# 3_6_1--esp32_-_1031_I2S.net
KiCad netlist of a schematic drawn in EasyEDA Pro
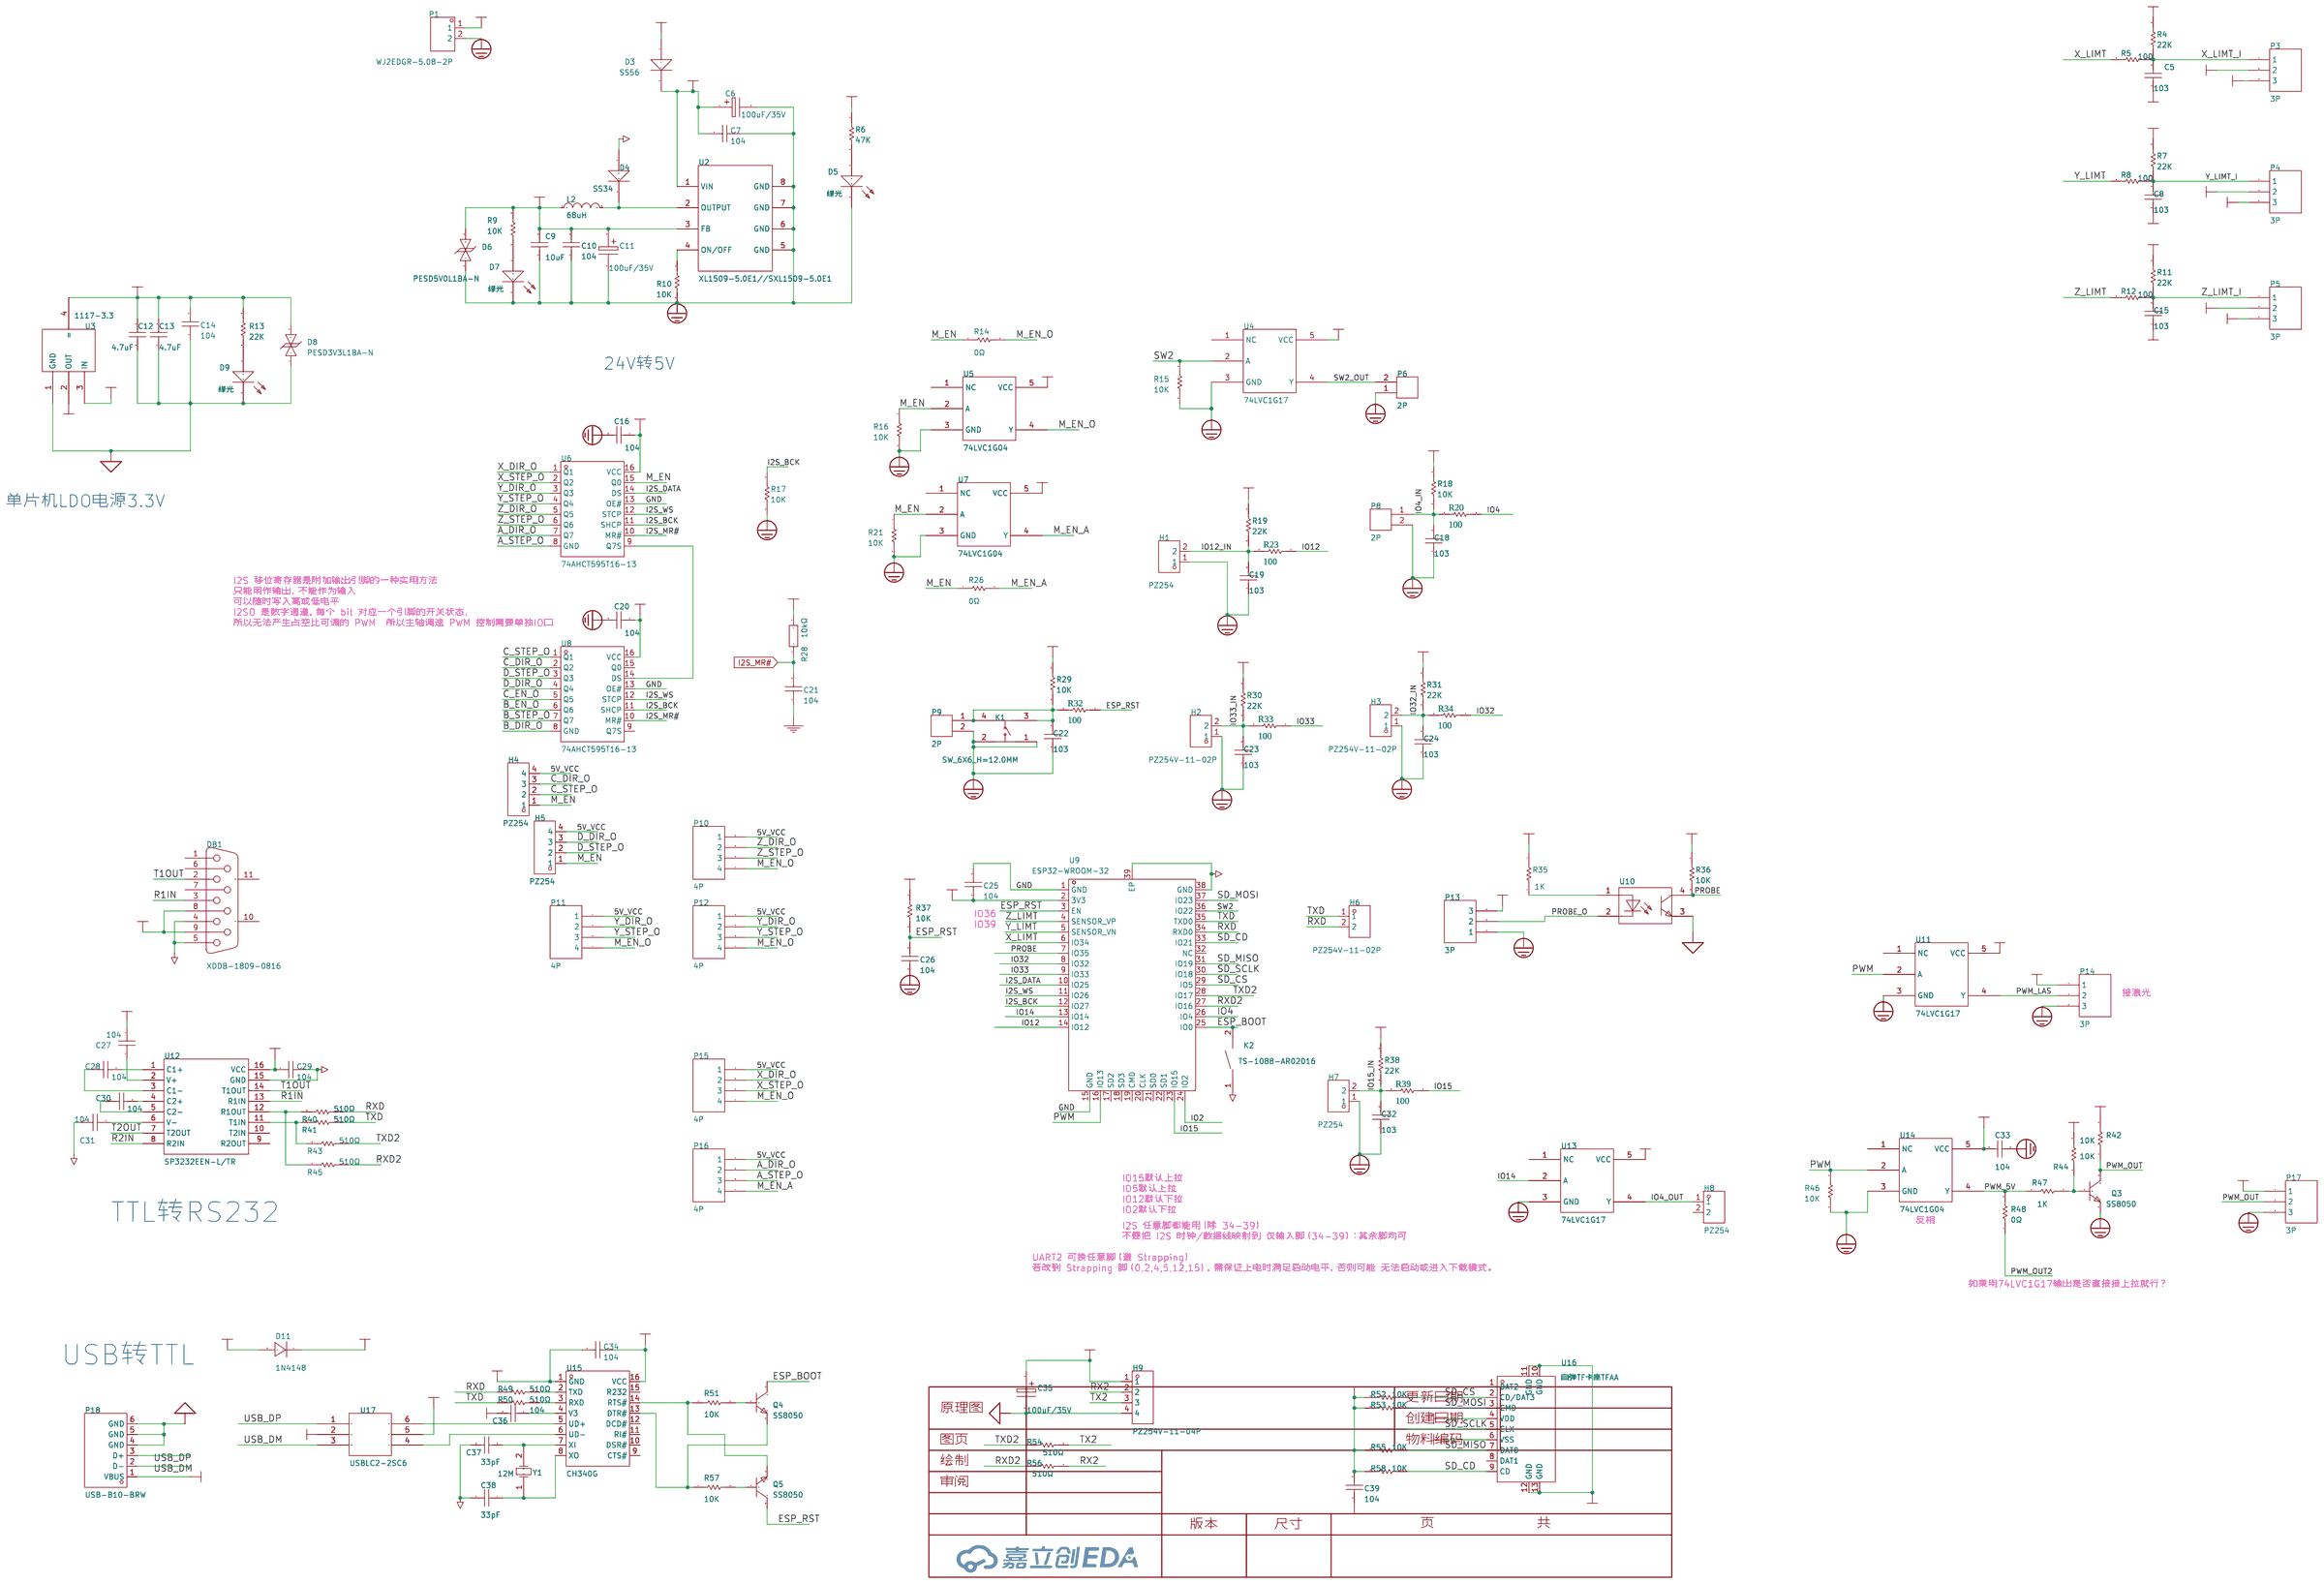
[diagram p0: schematic sheet]

(export (version "E")
  (design (tool "Eeschema 10.0.6"))
  (components
    (comp (ref "C5") (value "103") (footprint "easyedapro:11") (libsource (lib "easyedapro") (part "CAP")))
    (comp (ref "C6")
      (value "100uF/35V")
      (footprint "easyedapro:电解电容贴片10x10")
      (libsource (lib "easyedapro") (part "ELECTRO1"))
    )
    (comp (ref "C7")
      (value "104")
      (footprint "easyedapro:0603C")
      (description "Capacitor (Semiconductor SIM Model)")
      (libsource (lib "easyedapro") (part "Cap Semi"))
    )
    (comp (ref "C8") (value "103") (footprint "easyedapro:11") (libsource (lib "easyedapro") (part "CAP")))
    (comp (ref "C9") (value "10uF") (libsource (lib "") (part "CAP_1")))
    (comp (ref "C10")
      (value "104")
      (footprint "easyedapro:0603C")
      (description "Capacitor (Semiconductor SIM Model)")
      (libsource (lib "easyedapro") (part "Cap Semi"))
    )
    (comp (ref "C11")
      (value "100uF/35V")
      (footprint "easyedapro:0603C")
      (libsource (lib "easyedapro") (part "ELECTRO1"))
    )
    (comp (ref "C12") (value "4.7uF") (libsource (lib "") (part "CAP_1")))
    (comp (ref "C13") (value "4.7uF") (libsource (lib "") (part "CAP_1")))
    (comp (ref "C14")
      (value "104")
      (footprint "easyedapro:0603C")
      (description "Capacitor (Semiconductor SIM Model)")
      (libsource (lib "easyedapro") (part "Cap Semi"))
    )
    (comp (ref "C15") (value "103") (footprint "easyedapro:11") (libsource (lib "easyedapro") (part "CAP")))
    (comp (ref "C16")
      (value "104")
      (footprint "easyedapro:0603C")
      (description "Capacitor (Semiconductor SIM Model)")
      (libsource (lib "easyedapro") (part "Cap Semi"))
    )
    (comp (ref "C18") (value "103") (footprint "easyedapro:11") (libsource (lib "easyedapro") (part "CAP")))
    (comp (ref "C19") (value "103") (footprint "easyedapro:11") (libsource (lib "easyedapro") (part "CAP")))
    (comp (ref "C20")
      (value "104")
      (footprint "easyedapro:0603C")
      (description "Capacitor (Semiconductor SIM Model)")
      (libsource (lib "easyedapro") (part "Cap Semi"))
    )
    (comp (ref "C21")
      (value "104")
      (footprint "easyedapro:0603C")
      (description "Capacitor (Semiconductor SIM Model)")
      (libsource (lib "easyedapro") (part "Cap Semi"))
    )
    (comp (ref "C22") (value "103") (footprint "easyedapro:11") (libsource (lib "easyedapro") (part "CAP")))
    (comp (ref "C23") (value "103") (footprint "easyedapro:11") (libsource (lib "easyedapro") (part "CAP")))
    (comp (ref "C24") (value "103") (footprint "easyedapro:11") (libsource (lib "easyedapro") (part "CAP")))
    (comp (ref "C25")
      (value "104")
      (footprint "easyedapro:0603C")
      (description "Capacitor (Semiconductor SIM Model)")
      (libsource (lib "easyedapro") (part "Cap Semi"))
    )
    (comp (ref "C26")
      (value "104")
      (footprint "easyedapro:0603C")
      (description "Capacitor (Semiconductor SIM Model)")
      (libsource (lib "easyedapro") (part "Cap Semi"))
    )
    (comp (ref "C27")
      (value "104")
      (footprint "easyedapro:0603C")
      (description "Capacitor (Semiconductor SIM Model)")
      (libsource (lib "easyedapro") (part "Cap Semi"))
    )
    (comp (ref "C28")
      (value "104")
      (footprint "easyedapro:0603C")
      (description "Capacitor (Semiconductor SIM Model)")
      (libsource (lib "easyedapro") (part "Cap Semi"))
    )
    (comp (ref "C29")
      (value "104")
      (footprint "easyedapro:0603C")
      (description "Capacitor (Semiconductor SIM Model)")
      (libsource (lib "easyedapro") (part "Cap Semi"))
    )
    (comp (ref "C30")
      (value "104")
      (footprint "easyedapro:0603C")
      (description "Capacitor (Semiconductor SIM Model)")
      (libsource (lib "easyedapro") (part "Cap Semi"))
    )
    (comp (ref "C31")
      (value "104")
      (footprint "easyedapro:0603C")
      (description "Capacitor (Semiconductor SIM Model)")
      (libsource (lib "easyedapro") (part "Cap Semi"))
    )
    (comp (ref "C32") (value "103") (footprint "easyedapro:11") (libsource (lib "easyedapro") (part "CAP")))
    (comp (ref "C33")
      (value "104")
      (footprint "easyedapro:0603C")
      (description "Capacitor (Semiconductor SIM Model)")
      (libsource (lib "easyedapro") (part "Cap Semi"))
    )
    (comp (ref "C34")
      (value "104")
      (footprint "easyedapro:0603C")
      (description "Capacitor (Semiconductor SIM Model)")
      (libsource (lib "easyedapro") (part "Cap Semi"))
    )
    (comp (ref "C35")
      (value "100uF/35V")
      (footprint "easyedapro:电解电容贴片10x10")
      (libsource (lib "easyedapro") (part "ELECTRO1"))
    )
    (comp (ref "C36")
      (value "104")
      (footprint "easyedapro:0603C")
      (description "Capacitor (Semiconductor SIM Model)")
      (libsource (lib "easyedapro") (part "Cap Semi"))
    )
    (comp (ref "C37")
      (value "18pF")
      (footprint "easyedapro:0603C")
      (description "Capacitor (Semiconductor SIM Model)")
      (libsource (lib "easyedapro") (part "Cap Semi"))
    )
    (comp (ref "C38")
      (value "18pF")
      (footprint "easyedapro:0603C")
      (description "Capacitor (Semiconductor SIM Model)")
      (libsource (lib "easyedapro") (part "Cap Semi"))
    )
    (comp (ref "C39")
      (value "104")
      (footprint "easyedapro:11")
      (description "Capacitor (Semiconductor SIM Model)")
      (libsource (lib "easyedapro") (part "Cap Semi"))
    )
    (comp (ref "D3") (value "SS56") (footprint "easyedapro:SMA") (libsource (lib "") (part "1N4148_1")))
    (comp (ref "D4") (value "SS34") (libsource (lib "easyedapro") (part "1N4148")))
    (comp (ref "D5")
      (value "绿光")
      (footprint "easyedapro:0603LED")
      (libsource (lib "easyedapro") (part "LED"))
    )
    (comp (ref "D6")
      (value "PESD5V0L1BA-N")
      (footprint "easyedapro:SOD-523_L1.2-W0.8-LS1.6-BI")
      (description "极性:Bidirectional;反向关断电压（典型值）:5V (Max);击穿电压（最小值）:6V;箝位电压:15V;峰值脉冲电流（10/1000us）:5A (8/20us);")
      (fields (field (name "Manufacturer") "BORN伯恩半导体"))
      (libsource (lib "easyedapro") (part "PESD5V0S1BBN"))
    )
    (comp (ref "D7")
      (value "绿光")
      (footprint "easyedapro:0603LED")
      (libsource (lib "easyedapro") (part "LED"))
    )
    (comp (ref "D8")
      (value "PESD3V3L1BA-N")
      (footprint "easyedapro:SOD-523_L1.2-W0.8-LS1.6-BI")
      (description "极性:Bidirectional;反向关断电压（典型值）:5V (Max);击穿电压（最小值）:6V;箝位电压:15V;峰值脉冲电流（10/1000us）:5A (8/20us);")
      (fields (field (name "Manufacturer") "BORN伯恩半导体"))
      (libsource (lib "easyedapro") (part "PESD5V0S1BBN"))
    )
    (comp (ref "D9")
      (value "绿光")
      (footprint "easyedapro:0603LED")
      (libsource (lib "easyedapro") (part "LED"))
    )
    (comp (ref "D11")
      (value "1N4148")
      (footprint "easyedapro:SOD-123_L2.8-W1.8-LS3.7-RD")
      (fields (field (name "Manufacturer") "VISHAY(威世)"))
      (libsource (lib "easyedapro") (part "1N4148W-E3-08"))
    )
    (comp (ref "DB1")
      (value "XDDB-1809-0816")
      (footprint "easyedapro:DB9-TH_LD09P33E4GV00LF")
      (description "连接器类型:常规D-Sub;公母:公;总PIN位数:9P;安装方式:弯插;排数:2;额定电流-信号脚:3A;工作温度范围:-40°C~+85°C;")
      (fields (field (name "Manufacturer") "LX(连欣科技)"))
      (libsource (lib "easyedapro") (part "XDDB-1809-0816"))
    )
    (comp (ref "H1")
      (value "PZ254")
      (footprint "easyedapro:HDR-TH_2P-P2.54-V-M")
      (fields (field (name "Manufacturer") "XFCN(兴飞)"))
      (libsource (lib "easyedapro") (part "PZ254V-11-02P"))
    )
    (comp (ref "H2")
      (value "PZ254V-11-02P")
      (footprint "easyedapro:HDR-TH_2P-P2.54-V-M")
      (fields (field (name "Manufacturer") "XFCN(兴飞)"))
      (libsource (lib "easyedapro") (part "PZ254V-11-02P"))
    )
    (comp (ref "H3")
      (value "PZ254V-11-02P")
      (footprint "easyedapro:HDR-TH_2P-P2.54-V-M")
      (fields (field (name "Manufacturer") "XFCN(兴飞)"))
      (libsource (lib "easyedapro") (part "PZ254V-11-02P"))
    )
    (comp (ref "H4")
      (value "PZ254")
      (footprint "easyedapro:HDR-TH_4P-P2.54-V-M")
      (fields (field (name "Manufacturer") "XFCN(兴飞)"))
      (libsource (lib "easyedapro") (part "PZ254V-11-04P_C2691448"))
    )
    (comp (ref "H5")
      (value "PZ254")
      (footprint "easyedapro:HDR-TH_4P-P2.54-V-M")
      (fields (field (name "Manufacturer") "XFCN(兴飞)"))
      (libsource (lib "easyedapro") (part "PZ254V-11-04P_C2691448"))
    )
    (comp (ref "H6")
      (value "PZ254V-11-02P")
      (footprint "easyedapro:HDR-TH_2P-P2.54-V-M")
      (fields (field (name "Manufacturer") "XFCN(兴飞)"))
      (libsource (lib "easyedapro") (part "PZ254V-11-02P"))
    )
    (comp (ref "H7")
      (value "PZ254")
      (footprint "easyedapro:HDR-TH_2P-P2.54-V-M")
      (fields (field (name "Manufacturer") "XFCN(兴飞)"))
      (libsource (lib "easyedapro") (part "PZ254V-11-02P"))
    )
    (comp (ref "H8")
      (value "PZ254")
      (footprint "easyedapro:HDR-TH_2P-P2.54-V-M")
      (fields (field (name "Manufacturer") "XFCN(兴飞)"))
      (libsource (lib "easyedapro") (part "PZ254V-11-02P"))
    )
    (comp (ref "H9")
      (value "PZ254V-11-04P")
      (footprint "easyedapro:HDR-TH_4P-P2.54-V-M")
      (fields (field (name "Manufacturer") "XFCN(兴飞)"))
      (libsource (lib "easyedapro") (part "PZ254V-11-04P_C2691448"))
    )
    (comp (ref "K1")
      (value "SW_6X6_H=12.0MM")
      (footprint "easyedapro:KEY-SMD_4P-L6.0-W6.0-P4.50-LS9.0")
      (libsource (lib "easyedapro") (part "SW_6X6_H=12.0MM"))
    )
    (comp (ref "K2")
      (value "TS-1088-AR02016")
      (footprint "easyedapro:SW-SMD_L3.9-W3.0-P4.45")
      (fields (field (name "Manufacturer") "XUNPU(讯普)"))
      (libsource (lib "easyedapro") (part "TS-1088-AR02016"))
    )
    (comp (ref "L2")
      (value "68uH")
      (footprint "easyedapro:IND-SMD_L7.0-W7.0_SMDRI74-330MT")
      (description "电感值:33uH;精度:±20%;额定电流:960mA;饱和电流(Isat):1.8A;类型:屏蔽电感;")
      (fields (field (name "Manufacturer Part") "SMDRI74-330MT") (field (name "Manufacturer") "SXN(顺翔诺)"))
      (libsource (lib "easyedapro") (part "SMDRI74-330MT"))
    )
    (comp (ref "P1")
      (value "WJ2EDGR-5.08-2P")
      (footprint "easyedapro:CONN-TH_WJ2EDGR-5.08-2P")
      (description "每排PIN数:2;安装方式:弯针;排数:1;间距:5.08mm;连接器类型:板端/插座-开口;")
      (fields (field (name "Manufacturer") "KANGNEX(康奈克斯电气)"))
      (libsource (lib "easyedapro") (part "WJ2EDGR-5.08-2P"))
    )
    (comp (ref "P3")
      (value "3P")
      (footprint "easyedapro:HDR1X3_CON")
      (libsource (lib "easyedapro") (part "3P"))
    )
    (comp (ref "P4")
      (value "3P")
      (footprint "easyedapro:HDR1X3_CON")
      (libsource (lib "easyedapro") (part "3P"))
    )
    (comp (ref "P5")
      (value "3P")
      (footprint "easyedapro:HDR1X3_CON")
      (libsource (lib "easyedapro") (part "3P"))
    )
    (comp (ref "P6") (value "2P") (libsource (lib "easyedapro") (part "2P")))
    (comp (ref "P8") (value "2P") (libsource (lib "easyedapro") (part "2P")))
    (comp (ref "P9") (value "2P") (libsource (lib "easyedapro") (part "2P")))
    (comp (ref "P10")
      (value "4P")
      (footprint "easyedapro:HDR1X4_CON")
      (libsource (lib "easyedapro") (part "4P"))
    )
    (comp (ref "P11")
      (value "4P")
      (footprint "easyedapro:HDR1X4_CON")
      (libsource (lib "easyedapro") (part "4P"))
    )
    (comp (ref "P12")
      (value "4P")
      (footprint "easyedapro:HDR1X4_CON")
      (libsource (lib "easyedapro") (part "4P"))
    )
    (comp (ref "P13")
      (value "3P")
      (footprint "easyedapro:HDR1X3_CON")
      (libsource (lib "easyedapro") (part "3P"))
    )
    (comp (ref "P14")
      (value "3P")
      (footprint "easyedapro:HDR1X3_CON")
      (libsource (lib "easyedapro") (part "3P"))
    )
    (comp (ref "P15")
      (value "4P")
      (footprint "easyedapro:HDR1X4_CON")
      (libsource (lib "easyedapro") (part "4P"))
    )
    (comp (ref "P16")
      (value "4P")
      (footprint "easyedapro:HDR1X4_CON")
      (libsource (lib "easyedapro") (part "4P"))
    )
    (comp (ref "P17")
      (value "3P")
      (footprint "easyedapro:HDR1X3_CON")
      (libsource (lib "easyedapro") (part "3P"))
    )
    (comp (ref "P18")
      (value "USB-B10-BRW")
      (footprint "easyedapro:USB-B-TH_USB-B10-BRW")
      (fields (field (name "Manufacturer") "XUNPU(讯普)"))
      (libsource (lib "easyedapro") (part "USB-B10-BRW"))
    )
    (comp (ref "Q3")
      (value "SS8050")
      (footprint "easyedapro:SOT-23-3_L2.9-W1.3-P1.90-LS2.4-BR")
      (fields (field (name "Manufacturer") "CJ（江苏长电/长晶）"))
      (libsource (lib "easyedapro") (part "SS8050_C2150"))
    )
    (comp (ref "Q4")
      (value "SS8050")
      (footprint "easyedapro:SOT-23-3_L2.9-W1.3-P1.90-LS2.4-BR")
      (fields (field (name "Manufacturer") "Doeshare(德芯)"))
      (libsource (lib "easyedapro") (part "SS8050_C2931717"))
    )
    (comp (ref "Q5")
      (value "SS8050")
      (footprint "easyedapro:SOT-23-3_L2.9-W1.3-P1.90-LS2.4-BR")
      (fields (field (name "Manufacturer") "Doeshare(德芯)"))
      (libsource (lib "easyedapro") (part "SS8050_C2931717"))
    )
    (comp (ref "R4")
      (value "22K")
      (footprint "easyedapro:10")
      (description "Resistor")
      (libsource (lib "easyedapro") (part "RES"))
    )
    (comp (ref "R5")
      (value "100")
      (footprint "easyedapro:10")
      (description "Resistor")
      (libsource (lib "easyedapro") (part "RES"))
    )
    (comp (ref "R6")
      (value "47K")
      (footprint "easyedapro:0603R")
      (description "Resistor")
      (libsource (lib "easyedapro") (part "RES"))
    )
    (comp (ref "R7")
      (value "22K")
      (footprint "easyedapro:10")
      (description "Resistor")
      (libsource (lib "easyedapro") (part "RES"))
    )
    (comp (ref "R8")
      (value "100")
      (footprint "easyedapro:10")
      (description "Resistor")
      (libsource (lib "easyedapro") (part "RES"))
    )
    (comp (ref "R9")
      (value "10K")
      (footprint "easyedapro:0603R")
      (description "Resistor")
      (libsource (lib "easyedapro") (part "RES"))
    )
    (comp (ref "R10")
      (value "10K")
      (footprint "easyedapro:0603R")
      (description "Resistor")
      (libsource (lib "easyedapro") (part "RES"))
    )
    (comp (ref "R11")
      (value "22K")
      (footprint "easyedapro:10")
      (description "Resistor")
      (libsource (lib "easyedapro") (part "RES"))
    )
    (comp (ref "R12")
      (value "100")
      (footprint "easyedapro:10")
      (description "Resistor")
      (libsource (lib "easyedapro") (part "RES"))
    )
    (comp (ref "R13")
      (value "10K")
      (footprint "easyedapro:0603R")
      (description "Resistor")
      (libsource (lib "easyedapro") (part "RES"))
    )
    (comp (ref "R14")
      (value "0Ω")
      (description "Resistor")
      (fields (field (name "Publisher") "Altium Limited"))
      (libsource (lib "") (part "RES_1"))
    )
    (comp (ref "R15")
      (value "10K")
      (description "Resistor")
      (fields (field (name "Publisher") "Altium Limited"))
      (libsource (lib "") (part "RES_1"))
    )
    (comp (ref "R16")
      (value "10K")
      (description "Resistor")
      (fields (field (name "Publisher") "Altium Limited"))
      (libsource (lib "") (part "RES_1"))
    )
    (comp (ref "R17")
      (value "10K")
      (footprint "easyedapro:0603R")
      (description "Resistor")
      (libsource (lib "easyedapro") (part "RES"))
    )
    (comp (ref "R18")
      (value "10K")
      (footprint "easyedapro:0603R")
      (description "Resistor")
      (libsource (lib "easyedapro") (part "RES"))
    )
    (comp (ref "R19")
      (value "10K")
      (footprint "easyedapro:0603R")
      (description "Resistor")
      (libsource (lib "easyedapro") (part "RES"))
    )
    (comp (ref "R20")
      (value "100")
      (description "Resistor")
      (fields (field (name "Publisher") "Altium Limited"))
      (libsource (lib "") (part "RES_1"))
    )
    (comp (ref "R21")
      (value "10K")
      (description "Resistor")
      (fields (field (name "Publisher") "Altium Limited"))
      (libsource (lib "") (part "RES_1"))
    )
    (comp (ref "R23")
      (value "100")
      (description "Resistor")
      (fields (field (name "Publisher") "Altium Limited"))
      (libsource (lib "") (part "RES_1"))
    )
    (comp (ref "R26")
      (value "0Ω")
      (description "Resistor")
      (fields (field (name "Publisher") "Altium Limited"))
      (libsource (lib "") (part "RES_1"))
    )
    (comp (ref "R28")
      (value "10kΩ")
      (footprint "easyedapro:R0603")
      (fields (field (name "Manufacturer Part") "0603WAF1002T5E") (field (name "Manufacturer") "UniOhm"))
      (libsource (lib "easyedapro") (part "10kΩ"))
    )
    (comp (ref "R29")
      (value "10K")
      (footprint "easyedapro:0603R")
      (description "Resistor")
      (libsource (lib "easyedapro") (part "RES"))
    )
    (comp (ref "R30")
      (value "10K")
      (footprint "easyedapro:0603R")
      (description "Resistor")
      (libsource (lib "easyedapro") (part "RES"))
    )
    (comp (ref "R31")
      (value "10K")
      (footprint "easyedapro:0603R")
      (description "Resistor")
      (libsource (lib "easyedapro") (part "RES"))
    )
    (comp (ref "R32")
      (value "100")
      (description "Resistor")
      (fields (field (name "Publisher") "Altium Limited"))
      (libsource (lib "") (part "RES_1"))
    )
    (comp (ref "R33")
      (value "100")
      (description "Resistor")
      (fields (field (name "Publisher") "Altium Limited"))
      (libsource (lib "") (part "RES_1"))
    )
    (comp (ref "R34")
      (value "100")
      (description "Resistor")
      (fields (field (name "Publisher") "Altium Limited"))
      (libsource (lib "") (part "RES_1"))
    )
    (comp (ref "R35")
      (value "1K")
      (footprint "easyedapro:0603R")
      (description "Resistor")
      (libsource (lib "easyedapro") (part "RES"))
    )
    (comp (ref "R36")
      (value "10K")
      (footprint "easyedapro:0603R")
      (description "Resistor")
      (libsource (lib "easyedapro") (part "RES"))
    )
    (comp (ref "R37")
      (value "10K")
      (footprint "easyedapro:0603R")
      (description "Resistor")
      (libsource (lib "easyedapro") (part "RES"))
    )
    (comp (ref "R38")
      (value "10K")
      (footprint "easyedapro:0603R")
      (description "Resistor")
      (libsource (lib "easyedapro") (part "RES"))
    )
    (comp (ref "R39")
      (value "100")
      (description "Resistor")
      (fields (field (name "Publisher") "Altium Limited"))
      (libsource (lib "") (part "RES_1"))
    )
    (comp (ref "R40")
      (value "510Ω")
      (footprint "easyedapro:0603R")
      (description "Resistor")
      (libsource (lib "easyedapro") (part "RES"))
    )
    (comp (ref "R41")
      (value "510Ω")
      (footprint "easyedapro:0603R")
      (description "Resistor")
      (libsource (lib "easyedapro") (part "RES"))
    )
    (comp (ref "R42")
      (value "10K")
      (description "Resistor")
      (fields (field (name "Publisher") "Altium Limited"))
      (libsource (lib "") (part "RES_1"))
    )
    (comp (ref "R43")
      (value "510Ω")
      (footprint "easyedapro:0603R")
      (description "Resistor")
      (libsource (lib "easyedapro") (part "RES"))
    )
    (comp (ref "R44")
      (value "10K")
      (description "Resistor")
      (fields (field (name "Publisher") "Altium Limited"))
      (libsource (lib "") (part "RES_1"))
    )
    (comp (ref "R45")
      (value "510Ω")
      (footprint "easyedapro:0603R")
      (description "Resistor")
      (libsource (lib "easyedapro") (part "RES"))
    )
    (comp (ref "R46")
      (value "10K")
      (description "Resistor")
      (fields (field (name "Publisher") "Altium Limited"))
      (libsource (lib "") (part "RES_1"))
    )
    (comp (ref "R47")
      (value "1K")
      (description "Resistor")
      (fields (field (name "Publisher") "Altium Limited"))
      (libsource (lib "") (part "RES_1"))
    )
    (comp (ref "R48")
      (value "0Ω")
      (description "Resistor")
      (fields (field (name "Publisher") "Altium Limited"))
      (libsource (lib "") (part "RES_1"))
    )
    (comp (ref "R49")
      (value "510Ω")
      (footprint "easyedapro:0603R")
      (description "Resistor")
      (libsource (lib "easyedapro") (part "RES"))
    )
    (comp (ref "R50")
      (value "510Ω")
      (footprint "easyedapro:0603R")
      (description "Resistor")
      (libsource (lib "easyedapro") (part "RES"))
    )
    (comp (ref "R51")
      (value "10K")
      (footprint "easyedapro:0603R")
      (description "Resistor")
      (libsource (lib "easyedapro") (part "RES"))
    )
    (comp (ref "R52")
      (value "10K")
      (footprint "easyedapro:10")
      (description "Resistor")
      (libsource (lib "easyedapro") (part "RES"))
    )
    (comp (ref "R53")
      (value "10K")
      (footprint "easyedapro:10")
      (description "Resistor")
      (libsource (lib "easyedapro") (part "RES"))
    )
    (comp (ref "R54")
      (value "510Ω")
      (footprint "easyedapro:0603R")
      (description "Resistor")
      (libsource (lib "easyedapro") (part "RES"))
    )
    (comp (ref "R55")
      (value "10K")
      (footprint "easyedapro:10")
      (description "Resistor")
      (libsource (lib "easyedapro") (part "RES"))
    )
    (comp (ref "R56")
      (value "510Ω")
      (footprint "easyedapro:0603R")
      (description "Resistor")
      (libsource (lib "easyedapro") (part "RES"))
    )
    (comp (ref "R57")
      (value "10K")
      (footprint "easyedapro:0603R")
      (description "Resistor")
      (libsource (lib "easyedapro") (part "RES"))
    )
    (comp (ref "R58")
      (value "10K")
      (footprint "easyedapro:10")
      (description "Resistor")
      (libsource (lib "easyedapro") (part "RES"))
    )
    (comp (ref "U2")
      (value "XL1509-5.0E1//SXL1509-5.0E1")
      (footprint "easyedapro:SOIC-8_L5.0-W4.0-P1.27-LS6.0-BL")
      (description "功能类型:降压型;同步整流:-;输出通道数:-;拓扑结构:-;输入电压:-;输出电流(最大值):-;开关频率:-;")
      (fields (field (name "Manufacturer") "XLSEMI(芯龙)"))
      (libsource (lib "easyedapro") (part "XL1509-5.0E1"))
    )
    (comp (ref "U3")
      (value "1117-3.3")
      (footprint "easyedapro:SOT-223")
      (libsource (lib "easyedapro") (part "LM1117"))
    )
    (comp (ref "U4")
      (value "74LVC1G17")
      (footprint "easyedapro:SMD8")
      (libsource (lib "easyedapro") (part "74LVC1G04"))
    )
    (comp (ref "U5")
      (value "74LVC1G04")
      (footprint "easyedapro:SMD8")
      (libsource (lib "easyedapro") (part "74LVC1G04"))
    )
    (comp (ref "U6")
      (value "74AHCT595T16-13")
      (footprint "easyedapro:TSSOP-16_L5.0-W4.4-P0.65-LS6.4-BL")
      (description "功能:串行至串行或并行;工作电压:4.5V~5.5V;元件数:1;每个元件位数:8;")
      (fields (field (name "Manufacturer") "DIODES(美台)"))
      (libsource (lib "easyedapro") (part "74AHCT595T16-13"))
    )
    (comp (ref "U7")
      (value "74LVC1G04")
      (footprint "easyedapro:SMD8")
      (libsource (lib "easyedapro") (part "74LVC1G04"))
    )
    (comp (ref "U8")
      (value "74AHCT595T16-13")
      (footprint "easyedapro:TSSOP-16_L5.0-W4.4-P0.65-LS6.4-BL")
      (description "功能:串行至串行或并行;工作电压:4.5V~5.5V;元件数:1;每个元件位数:8;")
      (fields (field (name "Manufacturer") "DIODES(美台)"))
      (libsource (lib "easyedapro") (part "74AHCT595T16-13"))
    )
    (comp (ref "U9")
      (value "ESP32-WROOM-32")
      (footprint "easyedapro:WIFIM-SMD_ESP-WROOM-32")
      (description "WiFi+双模蓝牙 双核CPU 网口 顶配MCU 低功耗蓝牙 ESP32系列ESP-WROOM-32模组/ESP-32S 4MB")
      (fields (field (name "Manufacturer") "ESPRESSIF(乐鑫)"))
      (libsource (lib "easyedapro") (part "ESP-WROOM-32"))
    )
    (comp (ref "U10")
      (value "LTV-357T-C")
      (footprint "easyedapro:SOP-4_L4.4-W3.9-P2.54-LS7.0-TL")
      (fields (field (name "Manufacturer") "LITEON(光宝)"))
      (libsource (lib "easyedapro") (part "LTV-357T-C"))
    )
    (comp (ref "U11")
      (value "74LVC1G17")
      (footprint "easyedapro:SMD8")
      (libsource (lib "easyedapro") (part "74LVC1G04"))
    )
    (comp (ref "U12")
      (value "SP3232EEN-L/TR")
      (footprint "easyedapro:SOIC-16_L9.9-W3.9-P1.27-LS6.0-BL")
      (description "类型:收发器;数据速率:235Kbps;")
      (fields (field (name "Manufacturer") "MaxLinear(迈凌)"))
      (libsource (lib "easyedapro") (part "SP3232EEN-L/TR"))
    )
    (comp (ref "U13")
      (value "74LVC1G17")
      (footprint "easyedapro:SMD8")
      (libsource (lib "easyedapro") (part "74LVC1G04"))
    )
    (comp (ref "U14")
      (value "74LVC1G04")
      (footprint "easyedapro:SMD8")
      (libsource (lib "easyedapro") (part "74LVC1G04"))
    )
    (comp (ref "U15")
      (value "CH340G")
      (footprint "easyedapro:SOIC-16_L9.9-W3.9-P1.27-LS6.0-BL")
      (description "应用功能:收发器;接口协议:USB 2.0;数据速率:2Mbps;")
      (fields (field (name "Manufacturer") "WCH(南京沁恒)"))
      (libsource (lib "easyedapro") (part "CH340G"))
    )
    (comp (ref "U16")
      (value "自弹TF卡座TFAA")
      (footprint "easyedapro:SIM-SMD_C9900015645")
      (libsource (lib "easyedapro") (part "自弹TF卡座TFAA"))
    )
    (comp (ref "U17")
      (value "USBLC2-2SC6")
      (footprint "easyedapro:SOT-23-6")
      (libsource (lib "easyedapro") (part "DIP6"))
    )
    (comp (ref "Y1")
      (value "12M")
      (footprint "easyedapro:晶振贴片49SSMD")
      (description "Crystal Oscillator")
      (libsource (lib "easyedapro") (part "XTAL"))
    )
  )
  (nets
    (net (code "1") (name "/A_DIR_O") (class "Default")
      (node (ref "P16") (pin "2") (pinfunction "2_2") (pintype "unspecified"))
      (node (ref "U6") (pin "7") (pinfunction "Q7_7") (pintype "unspecified"))
    )
    (net (code "2") (name "/A_STEP_O") (class "Default")
      (node (ref "P16") (pin "3") (pinfunction "3_3") (pintype "unspecified"))
      (node (ref "U6") (pin "8") (pinfunction "GND_8") (pintype "unspecified"))
    )
    (net (code "3") (name "/B_DIR_O") (class "Default")
      (node (ref "U8") (pin "8") (pinfunction "GND_8") (pintype "unspecified"))
    )
    (net (code "4") (name "/B_EN_O") (class "Default")
      (node (ref "U8") (pin "6") (pinfunction "Q6_6") (pintype "unspecified"))
    )
    (net (code "5") (name "/B_STEP_O") (class "Default")
      (node (ref "U8") (pin "7") (pinfunction "Q7_7") (pintype "unspecified"))
    )
    (net (code "6") (name "/C_DIR_O") (class "Default")
      (node (ref "H4") (pin "3") (pinfunction "3_3") (pintype "unspecified"))
      (node (ref "U8") (pin "2") (pinfunction "Q2_2") (pintype "unspecified"))
    )
    (net (code "7") (name "/C_EN_O") (class "Default")
      (node (ref "U8") (pin "5") (pinfunction "Q5_5") (pintype "unspecified"))
    )
    (net (code "8") (name "/C_STEP_O") (class "Default")
      (node (ref "H4") (pin "2") (pinfunction "2_2") (pintype "unspecified"))
      (node (ref "U8") (pin "1") (pinfunction "Q1_1") (pintype "unspecified"))
    )
    (net (code "9") (name "/D_DIR_O") (class "Default")
      (node (ref "H5") (pin "3") (pinfunction "3_3") (pintype "unspecified"))
      (node (ref "U8") (pin "4") (pinfunction "Q4_4") (pintype "unspecified"))
    )
    (net (code "10") (name "/D_STEP_O") (class "Default")
      (node (ref "H5") (pin "2") (pinfunction "2_2") (pintype "unspecified"))
      (node (ref "U8") (pin "3") (pinfunction "Q3_3") (pintype "unspecified"))
    )
    (net (code "11") (name "/ESP_BOOT") (class "Default")
      (node (ref "K2") (pin "2") (pinfunction "2_2") (pintype "unspecified"))
      (node (ref "Q4") (pin "3") (pinfunction "C_3") (pintype "unspecified"))
      (node (ref "U9") (pin "25") (pinfunction "IO0_25") (pintype "unspecified"))
    )
    (net (code "12") (name "/ESP_RST") (class "Default")
      (node (ref "C26") (pin "2") (pinfunction "2_2") (pintype "unspecified"))
      (node (ref "Q5") (pin "3") (pinfunction "C_3") (pintype "unspecified"))
      (node (ref "R32") (pin "1") (pinfunction "1_1") (pintype "input"))
      (node (ref "R37") (pin "2") (pinfunction "2_2") (pintype "unspecified"))
      (node (ref "U9") (pin "3") (pinfunction "EN_3") (pintype "unspecified"))
    )
    (net (code "13") (name "/I2S_BCK") (class "Default")
      (node (ref "R17") (pin "1") (pinfunction "1_1") (pintype "unspecified"))
      (node (ref "U6") (pin "11") (pinfunction "SHCP_11") (pintype "unspecified"))
      (node (ref "U8") (pin "11") (pinfunction "SHCP_11") (pintype "unspecified"))
      (node (ref "U9") (pin "12") (pinfunction "IO27_12") (pintype "unspecified"))
    )
    (net (code "14") (name "/I2S_DATA") (class "Default")
      (node (ref "U6") (pin "14") (pinfunction "DS_14") (pintype "unspecified"))
      (node (ref "U9") (pin "10") (pinfunction "IO25_10") (pintype "unspecified"))
    )
    (net (code "15") (name "/I2S_WS") (class "Default")
      (node (ref "U6") (pin "12") (pinfunction "STCP_12") (pintype "unspecified"))
      (node (ref "U8") (pin "12") (pinfunction "STCP_12") (pintype "unspecified"))
      (node (ref "U9") (pin "11") (pinfunction "IO26_11") (pintype "unspecified"))
    )
    (net (code "16") (name "/IO2") (class "Default")
      (node (ref "U9") (pin "24") (pinfunction "IO2_24") (pintype "unspecified"))
    )
    (net (code "17") (name "/IO4") (class "Default")
      (node (ref "R20") (pin "1") (pinfunction "1_1") (pintype "input"))
      (node (ref "U9") (pin "26") (pinfunction "IO4_26") (pintype "unspecified"))
    )
    (net (code "18") (name "/IO4_IN") (class "Default")
      (node (ref "C18") (pin "2") (pinfunction "2_2") (pintype "unspecified"))
      (node (ref "P8") (pin "1") (pintype "input"))
      (node (ref "R18") (pin "2") (pinfunction "2_2") (pintype "unspecified"))
      (node (ref "R20") (pin "2") (pinfunction "2_2") (pintype "input"))
    )
    (net (code "19") (name "/IO4_OUT") (class "Default")
      (node (ref "H8") (pin "1") (pinfunction "1_1") (pintype "unspecified"))
      (node (ref "U13") (pin "4") (pinfunction "Y_4") (pintype "unspecified"))
    )
    (net (code "20") (name "/IO12") (class "Default")
      (node (ref "R23") (pin "1") (pinfunction "1_1") (pintype "input"))
      (node (ref "U9") (pin "14") (pinfunction "IO12_14") (pintype "unspecified"))
    )
    (net (code "21") (name "/IO12_IN") (class "Default")
      (node (ref "C19") (pin "2") (pinfunction "2_2") (pintype "unspecified"))
      (node (ref "H1") (pin "2") (pinfunction "2_2") (pintype "unspecified"))
      (node (ref "R19") (pin "2") (pinfunction "2_2") (pintype "unspecified"))
      (node (ref "R23") (pin "2") (pinfunction "2_2") (pintype "input"))
    )
    (net (code "22") (name "/IO14") (class "Default")
      (node (ref "U13") (pin "2") (pinfunction "A_2") (pintype "unspecified"))
      (node (ref "U9") (pin "13") (pinfunction "IO14_13") (pintype "unspecified"))
    )
    (net (code "23") (name "/IO15") (class "Default")
      (node (ref "R39") (pin "1") (pinfunction "1_1") (pintype "input"))
      (node (ref "U9") (pin "23") (pinfunction "IO15_23") (pintype "unspecified"))
    )
    (net (code "24") (name "/IO15_IN") (class "Default")
      (node (ref "C32") (pin "2") (pinfunction "2_2") (pintype "unspecified"))
      (node (ref "H7") (pin "2") (pinfunction "2_2") (pintype "unspecified"))
      (node (ref "R38") (pin "2") (pinfunction "2_2") (pintype "unspecified"))
      (node (ref "R39") (pin "2") (pinfunction "2_2") (pintype "input"))
    )
    (net (code "25") (name "/IO32") (class "Default")
      (node (ref "R34") (pin "1") (pinfunction "1_1") (pintype "input"))
      (node (ref "U9") (pin "8") (pinfunction "IO32_8") (pintype "unspecified"))
    )
    (net (code "26") (name "/IO32_IN") (class "Default")
      (node (ref "C24") (pin "2") (pinfunction "2_2") (pintype "unspecified"))
      (node (ref "H3") (pin "2") (pinfunction "2_2") (pintype "unspecified"))
      (node (ref "R31") (pin "2") (pinfunction "2_2") (pintype "unspecified"))
      (node (ref "R34") (pin "2") (pinfunction "2_2") (pintype "input"))
    )
    (net (code "27") (name "/IO33") (class "Default")
      (node (ref "R33") (pin "1") (pinfunction "1_1") (pintype "input"))
      (node (ref "U9") (pin "9") (pinfunction "IO33_9") (pintype "unspecified"))
    )
    (net (code "28") (name "/IO33_IN") (class "Default")
      (node (ref "C23") (pin "2") (pinfunction "2_2") (pintype "unspecified"))
      (node (ref "H2") (pin "2") (pinfunction "2_2") (pintype "unspecified"))
      (node (ref "R30") (pin "2") (pinfunction "2_2") (pintype "unspecified"))
      (node (ref "R33") (pin "2") (pinfunction "2_2") (pintype "input"))
    )
    (net (code "29") (name "/M_EN") (class "Default")
      (node (ref "H4") (pin "1") (pinfunction "1_1") (pintype "unspecified"))
      (node (ref "H5") (pin "1") (pinfunction "1_1") (pintype "unspecified"))
      (node (ref "R14") (pin "1") (pinfunction "1_1") (pintype "input"))
      (node (ref "R16") (pin "1") (pinfunction "1_1") (pintype "input"))
      (node (ref "R21") (pin "1") (pinfunction "1_1") (pintype "input"))
      (node (ref "R26") (pin "1") (pinfunction "1_1") (pintype "input"))
      (node (ref "U5") (pin "2") (pinfunction "A_2") (pintype "unspecified"))
      (node (ref "U6") (pin "15") (pinfunction "Q0_15") (pintype "unspecified"))
      (node (ref "U7") (pin "2") (pinfunction "A_2") (pintype "unspecified"))
    )
    (net (code "30") (name "/M_EN_A") (class "Default")
      (node (ref "P16") (pin "4") (pinfunction "4_4") (pintype "unspecified"))
      (node (ref "R26") (pin "2") (pinfunction "2_2") (pintype "input"))
      (node (ref "U7") (pin "4") (pinfunction "Y_4") (pintype "unspecified"))
    )
    (net (code "31") (name "/M_EN_O") (class "Default")
      (node (ref "P10") (pin "4") (pinfunction "4_4") (pintype "unspecified"))
      (node (ref "P11") (pin "4") (pinfunction "4_4") (pintype "unspecified"))
      (node (ref "P12") (pin "4") (pinfunction "4_4") (pintype "unspecified"))
      (node (ref "P15") (pin "4") (pinfunction "4_4") (pintype "unspecified"))
      (node (ref "R14") (pin "2") (pinfunction "2_2") (pintype "input"))
      (node (ref "U5") (pin "4") (pinfunction "Y_4") (pintype "unspecified"))
    )
    (net (code "32") (name "/PROBE") (class "Default")
      (node (ref "R36") (pin "2") (pinfunction "2_2") (pintype "unspecified"))
      (node (ref "U10") (pin "4") (pinfunction "4_4") (pintype "unspecified"))
      (node (ref "U9") (pin "7") (pinfunction "IO35_7") (pintype "unspecified"))
    )
    (net (code "33") (name "/PROBE_O") (class "Default")
      (node (ref "P13") (pin "2") (pinfunction "2_2") (pintype "unspecified"))
      (node (ref "U10") (pin "2") (pinfunction "2_2") (pintype "unspecified"))
    )
    (net (code "34") (name "/PWM") (class "Default")
      (node (ref "R46") (pin "1") (pinfunction "1_1") (pintype "input"))
      (node (ref "U11") (pin "2") (pinfunction "A_2") (pintype "unspecified"))
      (node (ref "U14") (pin "2") (pinfunction "A_2") (pintype "unspecified"))
      (node (ref "U9") (pin "16") (pinfunction "IO13_16") (pintype "unspecified"))
    )
    (net (code "35") (name "/PWM_5V") (class "Default")
      (node (ref "R47") (pin "1") (pinfunction "1_1") (pintype "input"))
      (node (ref "R48") (pin "2") (pinfunction "2_2") (pintype "input"))
      (node (ref "U14") (pin "4") (pinfunction "Y_4") (pintype "unspecified"))
    )
    (net (code "36") (name "/PWM_LAS") (class "Default")
      (node (ref "P14") (pin "2") (pinfunction "2_2") (pintype "unspecified"))
      (node (ref "U11") (pin "4") (pinfunction "Y_4") (pintype "unspecified"))
    )
    (net (code "37") (name "/PWM_OUT") (class "Default")
      (node (ref "P17") (pin "2") (pinfunction "2_2") (pintype "unspecified"))
      (node (ref "Q3") (pin "3") (pinfunction "C_3") (pintype "input"))
      (node (ref "R42") (pin "1") (pinfunction "1_1") (pintype "input"))
    )
    (net (code "38") (name "/PWM_OUT2") (class "Default")
      (node (ref "R48") (pin "1") (pinfunction "1_1") (pintype "input"))
    )
    (net (code "39") (name "/R1IN") (class "Default")
      (node (ref "DB1") (pin "3") (pinfunction "3_3") (pintype "input"))
      (node (ref "U12") (pin "13") (pinfunction "R1IN_13") (pintype "unspecified"))
    )
    (net (code "40") (name "/R2IN") (class "Default")
      (node (ref "U12") (pin "8") (pinfunction "R2IN_8") (pintype "unspecified"))
    )
    (net (code "41") (name "/RX2") (class "Default")
      (node (ref "H9") (pin "2") (pinfunction "2_2") (pintype "unspecified"))
      (node (ref "R56") (pin "2") (pinfunction "2_2") (pintype "unspecified"))
    )
    (net (code "42") (name "/RXD") (class "Default")
      (node (ref "H6") (pin "2") (pinfunction "2_2") (pintype "unspecified"))
      (node (ref "R40") (pin "1") (pinfunction "1_1") (pintype "unspecified"))
      (node (ref "R49") (pin "2") (pinfunction "2_2") (pintype "unspecified"))
      (node (ref "U9") (pin "34") (pinfunction "RXD0_34") (pintype "unspecified"))
    )
    (net (code "43") (name "/RXD2") (class "Default")
      (node (ref "R45") (pin "1") (pinfunction "1_1") (pintype "unspecified"))
      (node (ref "R56") (pin "1") (pinfunction "1_1") (pintype "unspecified"))
      (node (ref "U9") (pin "27") (pinfunction "IO16_27") (pintype "unspecified"))
    )
    (net (code "44") (name "/SD_CD") (class "Default")
      (node (ref "R58") (pin "1") (pinfunction "1_1") (pintype "unspecified"))
      (node (ref "U16") (pin "9") (pinfunction "CD_9") (pintype "unspecified"))
      (node (ref "U9") (pin "33") (pinfunction "IO21_33") (pintype "unspecified"))
    )
    (net (code "45") (name "/SD_CS") (class "Default")
      (node (ref "R52") (pin "1") (pinfunction "1_1") (pintype "unspecified"))
      (node (ref "U16") (pin "2") (pinfunction "CD/DAT3_2") (pintype "unspecified"))
      (node (ref "U9") (pin "29") (pinfunction "IO5_29") (pintype "unspecified"))
    )
    (net (code "46") (name "/SD_MISO") (class "Default")
      (node (ref "R55") (pin "1") (pinfunction "1_1") (pintype "unspecified"))
      (node (ref "U16") (pin "7") (pinfunction "DAT0_7") (pintype "unspecified"))
      (node (ref "U9") (pin "31") (pinfunction "IO19_31") (pintype "unspecified"))
    )
    (net (code "47") (name "/SD_MOSI") (class "Default")
      (node (ref "R53") (pin "1") (pinfunction "1_1") (pintype "unspecified"))
      (node (ref "U16") (pin "3") (pinfunction "CMD_3") (pintype "unspecified"))
      (node (ref "U9") (pin "37") (pinfunction "IO23_37") (pintype "unspecified"))
    )
    (net (code "48") (name "/SD_SCLK") (class "Default")
      (node (ref "U16") (pin "5") (pinfunction "CLX_5") (pintype "unspecified"))
      (node (ref "U9") (pin "30") (pinfunction "IO18_30") (pintype "unspecified"))
    )
    (net (code "49") (name "/SW2") (class "Default")
      (node (ref "R15") (pin "1") (pinfunction "1_1") (pintype "input"))
      (node (ref "U4") (pin "2") (pinfunction "A_2") (pintype "unspecified"))
      (node (ref "U9") (pin "36") (pinfunction "IO22_36") (pintype "unspecified"))
    )
    (net (code "50") (name "/SW2_OUT") (class "Default")
      (node (ref "P6") (pin "2") (pintype "input"))
      (node (ref "U4") (pin "4") (pinfunction "Y_4") (pintype "unspecified"))
    )
    (net (code "51") (name "/T1OUT") (class "Default")
      (node (ref "DB1") (pin "2") (pinfunction "2_2") (pintype "input"))
      (node (ref "U12") (pin "14") (pinfunction "T1OUT_14") (pintype "unspecified"))
    )
    (net (code "52") (name "/T2OUT") (class "Default")
      (node (ref "U12") (pin "7") (pinfunction "T2OUT_7") (pintype "unspecified"))
    )
    (net (code "53") (name "/TX2") (class "Default")
      (node (ref "H9") (pin "3") (pinfunction "3_3") (pintype "unspecified"))
      (node (ref "R54") (pin "2") (pinfunction "2_2") (pintype "unspecified"))
    )
    (net (code "54") (name "/TXD") (class "Default")
      (node (ref "H6") (pin "1") (pinfunction "1_1") (pintype "unspecified"))
      (node (ref "R41") (pin "1") (pinfunction "1_1") (pintype "unspecified"))
      (node (ref "R50") (pin "2") (pinfunction "2_2") (pintype "unspecified"))
      (node (ref "U9") (pin "35") (pinfunction "TXD0_35") (pintype "unspecified"))
    )
    (net (code "55") (name "/TXD2") (class "Default")
      (node (ref "R43") (pin "1") (pinfunction "1_1") (pintype "unspecified"))
      (node (ref "R54") (pin "1") (pinfunction "1_1") (pintype "unspecified"))
      (node (ref "U9") (pin "28") (pinfunction "IO17_28") (pintype "unspecified"))
    )
    (net (code "56") (name "/USB_DM") (class "Default")
      (node (ref "P18") (pin "2") (pinfunction "D-_2") (pintype "unspecified"))
      (node (ref "U17") (pin "3") (pinfunction "3_3") (pintype "unspecified"))
    )
    (net (code "57") (name "/USB_DP") (class "Default")
      (node (ref "P18") (pin "3") (pinfunction "D+_3") (pintype "unspecified"))
      (node (ref "U17") (pin "1") (pinfunction "1_1") (pintype "unspecified"))
    )
    (net (code "58") (name "/X_DIR_O") (class "Default")
      (node (ref "P15") (pin "2") (pinfunction "2_2") (pintype "unspecified"))
      (node (ref "U6") (pin "1") (pinfunction "Q1_1") (pintype "unspecified"))
    )
    (net (code "59") (name "/X_LIMT") (class "Default")
      (node (ref "R5") (pin "2") (pinfunction "2_2") (pintype "unspecified"))
      (node (ref "U9") (pin "6") (pinfunction "IO34_6") (pintype "unspecified"))
    )
    (net (code "60") (name "/X_LIMT_I") (class "Default")
      (node (ref "C5") (pin "2") (pinfunction "2_2") (pintype "unspecified"))
      (node (ref "P3") (pin "1") (pinfunction "1_1") (pintype "unspecified"))
      (node (ref "R4") (pin "1") (pinfunction "1_1") (pintype "unspecified"))
      (node (ref "R5") (pin "1") (pinfunction "1_1") (pintype "unspecified"))
    )
    (net (code "61") (name "/X_STEP_O") (class "Default")
      (node (ref "P15") (pin "3") (pinfunction "3_3") (pintype "unspecified"))
      (node (ref "U6") (pin "2") (pinfunction "Q2_2") (pintype "unspecified"))
    )
    (net (code "62") (name "/Y_DIR_O") (class "Default")
      (node (ref "P11") (pin "2") (pinfunction "2_2") (pintype "unspecified"))
      (node (ref "P12") (pin "2") (pinfunction "2_2") (pintype "unspecified"))
      (node (ref "U6") (pin "3") (pinfunction "Q3_3") (pintype "unspecified"))
    )
    (net (code "63") (name "/Y_LIMT") (class "Default")
      (node (ref "R8") (pin "2") (pinfunction "2_2") (pintype "unspecified"))
      (node (ref "U9") (pin "5") (pinfunction "SENSOR_VN_5") (pintype "unspecified"))
    )
    (net (code "64") (name "/Y_LIMT_I") (class "Default")
      (node (ref "C8") (pin "2") (pinfunction "2_2") (pintype "unspecified"))
      (node (ref "P4") (pin "1") (pinfunction "1_1") (pintype "unspecified"))
      (node (ref "R7") (pin "1") (pinfunction "1_1") (pintype "unspecified"))
      (node (ref "R8") (pin "1") (pinfunction "1_1") (pintype "unspecified"))
    )
    (net (code "65") (name "/Y_STEP_O") (class "Default")
      (node (ref "P11") (pin "3") (pinfunction "3_3") (pintype "unspecified"))
      (node (ref "P12") (pin "3") (pinfunction "3_3") (pintype "unspecified"))
      (node (ref "U6") (pin "4") (pinfunction "Q4_4") (pintype "unspecified"))
    )
    (net (code "66") (name "/Z_DIR_O") (class "Default")
      (node (ref "P10") (pin "2") (pinfunction "2_2") (pintype "unspecified"))
      (node (ref "U6") (pin "5") (pinfunction "Q5_5") (pintype "unspecified"))
    )
    (net (code "67") (name "/Z_LIMT") (class "Default")
      (node (ref "R12") (pin "2") (pinfunction "2_2") (pintype "unspecified"))
      (node (ref "U9") (pin "4") (pinfunction "SENSOR_VP_4") (pintype "unspecified"))
    )
    (net (code "68") (name "/Z_LIMT_I") (class "Default")
      (node (ref "C15") (pin "2") (pinfunction "2_2") (pintype "unspecified"))
      (node (ref "P5") (pin "1") (pinfunction "1_1") (pintype "unspecified"))
      (node (ref "R11") (pin "1") (pinfunction "1_1") (pintype "unspecified"))
      (node (ref "R12") (pin "1") (pinfunction "1_1") (pintype "unspecified"))
    )
    (net (code "69") (name "/Z_STEP_O") (class "Default")
      (node (ref "P10") (pin "3") (pinfunction "3_3") (pintype "unspecified"))
      (node (ref "U6") (pin "6") (pinfunction "Q6_6") (pintype "unspecified"))
    )
    (net (code "70") (name "3V3") (class "Default")
      (node (ref "C12") (pin "2") (pinfunction "2_2") (pintype "input"))
      (node (ref "C13") (pin "2") (pinfunction "2_2") (pintype "input"))
      (node (ref "C14") (pin "2") (pinfunction "2_2") (pintype "unspecified"))
      (node (ref "C25") (pin "1") (pinfunction "1_1") (pintype "unspecified"))
      (node (ref "C39") (pin "2") (pinfunction "2_2") (pintype "unspecified"))
      (node (ref "D8") (pin "2") (pinfunction "2_2") (pintype "input"))
      (node (ref "R13") (pin "2") (pinfunction "2_2") (pintype "unspecified"))
      (node (ref "R18") (pin "1") (pinfunction "1_1") (pintype "unspecified"))
      (node (ref "R29") (pin "1") (pinfunction "1_1") (pintype "unspecified"))
      (node (ref "R36") (pin "1") (pinfunction "1_1") (pintype "unspecified"))
      (node (ref "R37") (pin "1") (pinfunction "1_1") (pintype "unspecified"))
      (node (ref "R52") (pin "2") (pinfunction "2_2") (pintype "unspecified"))
      (node (ref "R53") (pin "2") (pinfunction "2_2") (pintype "unspecified"))
      (node (ref "R55") (pin "2") (pinfunction "2_2") (pintype "unspecified"))
      (node (ref "R58") (pin "2") (pinfunction "2_2") (pintype "unspecified"))
      (node (ref "U16") (pin "4") (pinfunction "VDD_4") (pintype "unspecified"))
      (node (ref "U3") (pin "2") (pinfunction "OUT_2") (pintype "unspecified"))
      (node (ref "U3") (pin "4") (pinfunction "=_4") (pintype "unspecified"))
      (node (ref "U9") (pin "2") (pinfunction "3V3_2") (pintype "unspecified"))
    )
    (net (code "71") (name "5V_VCC") (class "Default")
      (node (ref "C10") (pin "2") (pinfunction "2_2") (pintype "unspecified"))
      (node (ref "C11") (pin "1") (pintype "unspecified"))
      (node (ref "C16") (pin "1") (pinfunction "1_1") (pintype "unspecified"))
      (node (ref "C20") (pin "1") (pinfunction "1_1") (pintype "unspecified"))
      (node (ref "C27") (pin "1") (pinfunction "1_1") (pintype "unspecified"))
      (node (ref "C29") (pin "2") (pinfunction "2_2") (pintype "unspecified"))
      (node (ref "C33") (pin "2") (pinfunction "2_2") (pintype "unspecified"))
      (node (ref "C34") (pin "1") (pinfunction "1_1") (pintype "unspecified"))
      (node (ref "C35") (pin "1") (pintype "unspecified"))
      (node (ref "C9") (pin "1") (pinfunction "1_1") (pintype "input"))
      (node (ref "D11") (pin "1") (pinfunction "K_1") (pintype "input"))
      (node (ref "D6") (pin "2") (pinfunction "2_2") (pintype "input"))
      (node (ref "H4") (pin "4") (pinfunction "4_4") (pintype "unspecified"))
      (node (ref "H5") (pin "4") (pinfunction "4_4") (pintype "unspecified"))
      (node (ref "H9") (pin "1") (pinfunction "1_1") (pintype "unspecified"))
      (node (ref "L2") (pin "1") (pinfunction "1_1") (pintype "unspecified"))
      (node (ref "P10") (pin "1") (pinfunction "1_1") (pintype "unspecified"))
      (node (ref "P11") (pin "1") (pinfunction "1_1") (pintype "unspecified"))
      (node (ref "P12") (pin "1") (pinfunction "1_1") (pintype "unspecified"))
      (node (ref "P13") (pin "3") (pinfunction "3_3") (pintype "unspecified"))
      (node (ref "P15") (pin "1") (pinfunction "1_1") (pintype "unspecified"))
      (node (ref "P16") (pin "1") (pinfunction "1_1") (pintype "unspecified"))
      (node (ref "P17") (pin "1") (pinfunction "1_1") (pintype "unspecified"))
      (node (ref "P3") (pin "3") (pinfunction "3_3") (pintype "unspecified"))
      (node (ref "P4") (pin "3") (pinfunction "3_3") (pintype "unspecified"))
      (node (ref "P5") (pin "3") (pinfunction "3_3") (pintype "unspecified"))
      (node (ref "R11") (pin "2") (pinfunction "2_2") (pintype "unspecified"))
      (node (ref "R19") (pin "1") (pinfunction "1_1") (pintype "unspecified"))
      (node (ref "R28") (pin "2") (pinfunction "2_2") (pintype "input"))
      (node (ref "R30") (pin "1") (pinfunction "1_1") (pintype "unspecified"))
      (node (ref "R31") (pin "1") (pinfunction "1_1") (pintype "unspecified"))
      (node (ref "R35") (pin "1") (pinfunction "1_1") (pintype "unspecified"))
      (node (ref "R38") (pin "1") (pinfunction "1_1") (pintype "unspecified"))
      (node (ref "R4") (pin "2") (pinfunction "2_2") (pintype "unspecified"))
      (node (ref "R42") (pin "2") (pinfunction "2_2") (pintype "input"))
      (node (ref "R44") (pin "2") (pinfunction "2_2") (pintype "input"))
      (node (ref "R7") (pin "2") (pinfunction "2_2") (pintype "unspecified"))
      (node (ref "R9") (pin "2") (pinfunction "2_2") (pintype "unspecified"))
      (node (ref "U11") (pin "5") (pinfunction "VCC_5") (pintype "unspecified"))
      (node (ref "U12") (pin "16") (pinfunction "VCC_16") (pintype "unspecified"))
      (node (ref "U13") (pin "5") (pinfunction "VCC_5") (pintype "unspecified"))
      (node (ref "U14") (pin "5") (pinfunction "VCC_5") (pintype "unspecified"))
      (node (ref "U15") (pin "16") (pinfunction "VCC_16") (pintype "unspecified"))
      (node (ref "U2") (pin "3") (pinfunction "FB_3") (pintype "input"))
      (node (ref "U3") (pin "3") (pinfunction "IN_3") (pintype "unspecified"))
      (node (ref "U4") (pin "5") (pinfunction "VCC_5") (pintype "unspecified"))
      (node (ref "U5") (pin "5") (pinfunction "VCC_5") (pintype "unspecified"))
      (node (ref "U6") (pin "16") (pinfunction "VCC_16") (pintype "unspecified"))
      (node (ref "U7") (pin "5") (pinfunction "VCC_5") (pintype "unspecified"))
      (node (ref "U8") (pin "16") (pinfunction "VCC_16") (pintype "unspecified"))
    )
    (net (code "72") (name "24V") (class "Default")
      (node (ref "D3") (pin "1") (pinfunction "1_1") (pintype "unspecified"))
      (node (ref "DB1") (pin "8") (pinfunction "8_8") (pintype "input"))
      (node (ref "DB1") (pin "9") (pinfunction "9_9") (pintype "input"))
      (node (ref "P1") (pin "1") (pinfunction "1_1") (pintype "input"))
      (node (ref "P14") (pin "1") (pinfunction "1_1") (pintype "unspecified"))
      (node (ref "R6") (pin "2") (pinfunction "2_2") (pintype "unspecified"))
    )
    (net (code "73") (name "GND") (class "Default")
      (node (ref "C10") (pin "1") (pinfunction "1_1") (pintype "unspecified"))
      (node (ref "C11") (pin "2") (pintype "unspecified"))
      (node (ref "C12") (pin "1") (pinfunction "1_1") (pintype "input"))
      (node (ref "C13") (pin "1") (pinfunction "1_1") (pintype "input"))
      (node (ref "C14") (pin "1") (pinfunction "1_1") (pintype "unspecified"))
      (node (ref "C15") (pin "1") (pinfunction "1_1") (pintype "unspecified"))
      (node (ref "C16") (pin "2") (pinfunction "2_2") (pintype "unspecified"))
      (node (ref "C18") (pin "1") (pinfunction "1_1") (pintype "unspecified"))
      (node (ref "C19") (pin "1") (pinfunction "1_1") (pintype "unspecified"))
      (node (ref "C20") (pin "2") (pinfunction "2_2") (pintype "unspecified"))
      (node (ref "C21") (pin "1") (pinfunction "1_1") (pintype "unspecified"))
      (node (ref "C22") (pin "1") (pinfunction "1_1") (pintype "unspecified"))
      (node (ref "C23") (pin "1") (pinfunction "1_1") (pintype "unspecified"))
      (node (ref "C24") (pin "1") (pinfunction "1_1") (pintype "unspecified"))
      (node (ref "C25") (pin "2") (pinfunction "2_2") (pintype "unspecified"))
      (node (ref "C26") (pin "1") (pinfunction "1_1") (pintype "unspecified"))
      (node (ref "C29") (pin "1") (pinfunction "1_1") (pintype "unspecified"))
      (node (ref "C31") (pin "2") (pinfunction "2_2") (pintype "unspecified"))
      (node (ref "C32") (pin "1") (pinfunction "1_1") (pintype "unspecified"))
      (node (ref "C33") (pin "1") (pinfunction "1_1") (pintype "unspecified"))
      (node (ref "C34") (pin "2") (pinfunction "2_2") (pintype "unspecified"))
      (node (ref "C35") (pin "2") (pintype "unspecified"))
      (node (ref "C36") (pin "2") (pinfunction "2_2") (pintype "unspecified"))
      (node (ref "C37") (pin "2") (pinfunction "2_2") (pintype "unspecified"))
      (node (ref "C38") (pin "2") (pinfunction "2_2") (pintype "unspecified"))
      (node (ref "C39") (pin "1") (pinfunction "1_1") (pintype "unspecified"))
      (node (ref "C5") (pin "1") (pinfunction "1_1") (pintype "unspecified"))
      (node (ref "C6") (pin "2") (pintype "unspecified"))
      (node (ref "C7") (pin "1") (pinfunction "1_1") (pintype "unspecified"))
      (node (ref "C8") (pin "1") (pinfunction "1_1") (pintype "unspecified"))
      (node (ref "C9") (pin "2") (pinfunction "2_2") (pintype "input"))
      (node (ref "D4") (pin "1") (pinfunction "1_1") (pintype "input"))
      (node (ref "D5") (pin "2") (pinfunction "2_2") (pintype "unspecified"))
      (node (ref "D6") (pin "1") (pinfunction "1_1") (pintype "input"))
      (node (ref "D7") (pin "2") (pinfunction "2_2") (pintype "unspecified"))
      (node (ref "D8") (pin "1") (pinfunction "1_1") (pintype "input"))
      (node (ref "D9") (pin "2") (pinfunction "2_2") (pintype "unspecified"))
      (node (ref "DB1") (pin "4") (pinfunction "4_4") (pintype "input"))
      (node (ref "DB1") (pin "5") (pinfunction "5_5") (pintype "input"))
      (node (ref "H1") (pin "1") (pinfunction "1_1") (pintype "unspecified"))
      (node (ref "H2") (pin "1") (pinfunction "1_1") (pintype "unspecified"))
      (node (ref "H3") (pin "1") (pinfunction "1_1") (pintype "unspecified"))
      (node (ref "H7") (pin "1") (pinfunction "1_1") (pintype "unspecified"))
      (node (ref "H9") (pin "4") (pinfunction "4_4") (pintype "unspecified"))
      (node (ref "K1") (pin "1") (pinfunction "1_1") (pintype "unspecified"))
      (node (ref "K1") (pin "2") (pinfunction "2_2") (pintype "unspecified"))
      (node (ref "K2") (pin "1") (pinfunction "1_1") (pintype "unspecified"))
      (node (ref "P1") (pin "2") (pinfunction "2_2") (pintype "input"))
      (node (ref "P13") (pin "1") (pinfunction "1_1") (pintype "unspecified"))
      (node (ref "P14") (pin "3") (pinfunction "3_3") (pintype "unspecified"))
      (node (ref "P17") (pin "3") (pinfunction "3_3") (pintype "unspecified"))
      (node (ref "P18") (pin "4") (pinfunction "GND_4") (pintype "unspecified"))
      (node (ref "P18") (pin "5") (pinfunction "GND_5") (pintype "unspecified"))
      (node (ref "P18") (pin "6") (pinfunction "GND_6") (pintype "unspecified"))
      (node (ref "P3") (pin "2") (pinfunction "2_2") (pintype "unspecified"))
      (node (ref "P4") (pin "2") (pinfunction "2_2") (pintype "unspecified"))
      (node (ref "P5") (pin "2") (pinfunction "2_2") (pintype "unspecified"))
      (node (ref "P6") (pin "1") (pintype "input"))
      (node (ref "P8") (pin "2") (pintype "input"))
      (node (ref "P9") (pin "2") (pintype "input"))
      (node (ref "Q3") (pin "2") (pinfunction "E_2") (pintype "input"))
      (node (ref "R10") (pin "2") (pinfunction "2_2") (pintype "unspecified"))
      (node (ref "R15") (pin "2") (pinfunction "2_2") (pintype "input"))
      (node (ref "R16") (pin "2") (pinfunction "2_2") (pintype "input"))
      (node (ref "R17") (pin "2") (pinfunction "2_2") (pintype "unspecified"))
      (node (ref "R21") (pin "2") (pinfunction "2_2") (pintype "input"))
      (node (ref "R46") (pin "2") (pinfunction "2_2") (pintype "input"))
      (node (ref "U10") (pin "3") (pinfunction "3_3") (pintype "unspecified"))
      (node (ref "U11") (pin "3") (pinfunction "GND_3") (pintype "unspecified"))
      (node (ref "U12") (pin "15") (pinfunction "GND_15") (pintype "unspecified"))
      (node (ref "U13") (pin "3") (pinfunction "GND_3") (pintype "unspecified"))
      (node (ref "U14") (pin "3") (pinfunction "GND_3") (pintype "unspecified"))
      (node (ref "U15") (pin "1") (pinfunction "GND_1") (pintype "unspecified"))
      (node (ref "U16") (pin "10") (pinfunction "GND_10") (pintype "unspecified"))
      (node (ref "U16") (pin "11") (pinfunction "GND_11") (pintype "unspecified"))
      (node (ref "U16") (pin "12") (pinfunction "GND_12") (pintype "unspecified"))
      (node (ref "U16") (pin "13") (pinfunction "GND_13") (pintype "unspecified"))
      (node (ref "U16") (pin "6") (pinfunction "VSS_6") (pintype "unspecified"))
      (node (ref "U17") (pin "2") (pinfunction "2_2") (pintype "unspecified"))
      (node (ref "U2") (pin "5") (pinfunction "GND_5") (pintype "input"))
      (node (ref "U2") (pin "6") (pinfunction "GND_6") (pintype "input"))
      (node (ref "U2") (pin "7") (pinfunction "GND_7") (pintype "input"))
      (node (ref "U2") (pin "8") (pinfunction "GND_8") (pintype "input"))
      (node (ref "U3") (pin "1") (pinfunction "GND_1") (pintype "unspecified"))
      (node (ref "U4") (pin "3") (pinfunction "GND_3") (pintype "unspecified"))
      (node (ref "U5") (pin "3") (pinfunction "GND_3") (pintype "unspecified"))
      (node (ref "U6") (pin "13") (pinfunction "OE#_13") (pintype "unspecified"))
      (node (ref "U7") (pin "3") (pinfunction "GND_3") (pintype "unspecified"))
      (node (ref "U8") (pin "13") (pinfunction "OE#_13") (pintype "unspecified"))
      (node (ref "U9") (pin "1") (pinfunction "GND_1") (pintype "unspecified"))
      (node (ref "U9") (pin "15") (pinfunction "GND_15") (pintype "unspecified"))
      (node (ref "U9") (pin "38") (pinfunction "GND_38") (pintype "unspecified"))
      (node (ref "U9") (pin "39") (pinfunction "EP_39") (pintype "unspecified"))
    )
    (net (code "74") (name "I2S_MR#") (class "Default")
      (node (ref "C21") (pin "2") (pinfunction "2_2") (pintype "unspecified"))
      (node (ref "R28") (pin "1") (pinfunction "1_1") (pintype "input"))
      (node (ref "U6") (pin "10") (pinfunction "MR#_10") (pintype "unspecified"))
      (node (ref "U8") (pin "10") (pinfunction "MR#_10") (pintype "unspecified"))
    )
    (net (code "75") (name "Net-(C22-Pad2)") (class "Default")
      (node (ref "C22") (pin "2") (pinfunction "2_2") (pintype "unspecified"))
      (node (ref "K1") (pin "3") (pinfunction "3_3") (pintype "unspecified"))
      (node (ref "K1") (pin "4") (pinfunction "4_4") (pintype "unspecified"))
      (node (ref "P9") (pin "1") (pintype "input"))
      (node (ref "R29") (pin "2") (pinfunction "2_2") (pintype "unspecified"))
      (node (ref "R32") (pin "2") (pinfunction "2_2") (pintype "input"))
    )
    (net (code "76") (name "Net-(D5-Pad1)") (class "Default")
      (node (ref "D5") (pin "1") (pinfunction "1_1") (pintype "unspecified"))
      (node (ref "R6") (pin "1") (pinfunction "1_1") (pintype "unspecified"))
    )
    (net (code "77") (name "Net-(D7-Pad1)") (class "Default")
      (node (ref "D7") (pin "1") (pinfunction "1_1") (pintype "unspecified"))
      (node (ref "R9") (pin "1") (pinfunction "1_1") (pintype "unspecified"))
    )
    (net (code "78") (name "Net-(D9-Pad1)") (class "Default")
      (node (ref "D9") (pin "1") (pinfunction "1_1") (pintype "unspecified"))
      (node (ref "R13") (pin "1") (pinfunction "1_1") (pintype "unspecified"))
    )
    (net (code "79") (name "Net-(Q3-B)") (class "Default")
      (node (ref "Q3") (pin "1") (pinfunction "B_1") (pintype "input"))
      (node (ref "R44") (pin "1") (pinfunction "1_1") (pintype "input"))
      (node (ref "R47") (pin "2") (pinfunction "2_2") (pintype "input"))
    )
    (net (code "80") (name "Net-(Q4-B)") (class "Default")
      (node (ref "Q4") (pin "1") (pinfunction "B_1") (pintype "unspecified"))
      (node (ref "R51") (pin "2") (pinfunction "2_2") (pintype "unspecified"))
    )
    (net (code "81") (name "Net-(Q4-E)") (class "Default")
      (node (ref "Q4") (pin "2") (pinfunction "E_2") (pintype "unspecified"))
      (node (ref "R57") (pin "1") (pinfunction "1_1") (pintype "unspecified"))
      (node (ref "U15") (pin "13") (pinfunction "DTR#_13") (pintype "unspecified"))
    )
    (net (code "82") (name "Net-(Q5-B)") (class "Default")
      (node (ref "Q5") (pin "1") (pinfunction "B_1") (pintype "unspecified"))
      (node (ref "R57") (pin "2") (pinfunction "2_2") (pintype "unspecified"))
    )
    (net (code "83") (name "Net-(Q5-E)") (class "Default")
      (node (ref "Q5") (pin "2") (pinfunction "E_2") (pintype "unspecified"))
      (node (ref "R51") (pin "1") (pinfunction "1_1") (pintype "unspecified"))
      (node (ref "U15") (pin "14") (pinfunction "RTS#_14") (pintype "unspecified"))
    )
    (net (code "84") (name "Net-(R35-Pad2)") (class "Default")
      (node (ref "R35") (pin "2") (pinfunction "2_2") (pintype "unspecified"))
      (node (ref "U10") (pin "1") (pinfunction "1_1") (pintype "unspecified"))
    )
    (net (code "85") (name "Net-(U2-ON{slash}OFF)") (class "Default")
      (node (ref "R10") (pin "1") (pinfunction "1_1") (pintype "unspecified"))
      (node (ref "U2") (pin "4") (pinfunction "ON/OFF_4") (pintype "input"))
    )
    (net (code "86") (name "Net-(U2-OUTPUT)") (class "Default")
      (node (ref "D4") (pin "2") (pinfunction "2_2") (pintype "input"))
      (node (ref "L2") (pin "2") (pinfunction "2_2") (pintype "unspecified"))
      (node (ref "U2") (pin "2") (pinfunction "OUTPUT_2") (pintype "input"))
    )
    (net (code "87") (name "Net-(U6-Q7S)") (class "Default")
      (node (ref "U6") (pin "9") (pinfunction "Q7S_9") (pintype "unspecified"))
      (node (ref "U8") (pin "14") (pinfunction "DS_14") (pintype "unspecified"))
    )
    (net (code "88") (name "Net-(U12-C1+)") (class "Default")
      (node (ref "C28") (pin "2") (pinfunction "2_2") (pintype "unspecified"))
      (node (ref "U12") (pin "1") (pinfunction "C1+_1") (pintype "unspecified"))
    )
    (net (code "89") (name "Net-(U12-C1-)") (class "Default")
      (node (ref "C28") (pin "1") (pinfunction "1_1") (pintype "unspecified"))
      (node (ref "U12") (pin "3") (pinfunction "C1-_3") (pintype "unspecified"))
    )
    (net (code "90") (name "Net-(U12-C2+)") (class "Default")
      (node (ref "C30") (pin "2") (pinfunction "2_2") (pintype "unspecified"))
      (node (ref "U12") (pin "4") (pinfunction "C2+_4") (pintype "unspecified"))
    )
    (net (code "91") (name "Net-(U12-C2-)") (class "Default")
      (node (ref "C30") (pin "1") (pinfunction "1_1") (pintype "unspecified"))
      (node (ref "U12") (pin "5") (pinfunction "C2-_5") (pintype "unspecified"))
    )
    (net (code "92") (name "Net-(U12-R1OUT)") (class "Default")
      (node (ref "R40") (pin "2") (pinfunction "2_2") (pintype "unspecified"))
      (node (ref "R45") (pin "2") (pinfunction "2_2") (pintype "unspecified"))
      (node (ref "U12") (pin "12") (pinfunction "R1OUT_12") (pintype "unspecified"))
    )
    (net (code "93") (name "Net-(U12-T1IN)") (class "Default")
      (node (ref "R41") (pin "2") (pinfunction "2_2") (pintype "unspecified"))
      (node (ref "R43") (pin "2") (pinfunction "2_2") (pintype "unspecified"))
      (node (ref "U12") (pin "11") (pinfunction "T1IN_11") (pintype "unspecified"))
    )
    (net (code "94") (name "Net-(U12-V+)") (class "Default")
      (node (ref "C27") (pin "2") (pinfunction "2_2") (pintype "unspecified"))
      (node (ref "U12") (pin "2") (pinfunction "V+_2") (pintype "unspecified"))
    )
    (net (code "95") (name "Net-(U12-V-)") (class "Default")
      (node (ref "C31") (pin "1") (pinfunction "1_1") (pintype "unspecified"))
      (node (ref "U12") (pin "6") (pinfunction "V-_6") (pintype "unspecified"))
    )
    (net (code "96") (name "Net-(U15-RXD)") (class "Default")
      (node (ref "R50") (pin "1") (pinfunction "1_1") (pintype "unspecified"))
      (node (ref "U15") (pin "3") (pinfunction "RXD_3") (pintype "unspecified"))
    )
    (net (code "97") (name "Net-(U15-TXD)") (class "Default")
      (node (ref "R49") (pin "1") (pinfunction "1_1") (pintype "unspecified"))
      (node (ref "U15") (pin "2") (pinfunction "TXD_2") (pintype "unspecified"))
    )
    (net (code "98") (name "Net-(U15-UD+)") (class "Default")
      (node (ref "U15") (pin "5") (pinfunction "UD+_5") (pintype "unspecified"))
      (node (ref "U17") (pin "6") (pinfunction "6_6") (pintype "unspecified"))
    )
    (net (code "99") (name "Net-(U15-UD-)") (class "Default")
      (node (ref "U15") (pin "6") (pinfunction "UD-_6") (pintype "unspecified"))
      (node (ref "U17") (pin "4") (pinfunction "4_4") (pintype "unspecified"))
    )
    (net (code "100") (name "Net-(U15-V3)") (class "Default")
      (node (ref "C36") (pin "1") (pinfunction "1_1") (pintype "unspecified"))
      (node (ref "U15") (pin "4") (pinfunction "V3_4") (pintype "unspecified"))
    )
    (net (code "101") (name "Net-(U15-XI)") (class "Default")
      (node (ref "C37") (pin "1") (pinfunction "1_1") (pintype "unspecified"))
      (node (ref "U15") (pin "7") (pinfunction "XI_7") (pintype "unspecified"))
      (node (ref "Y1") (pin "2") (pinfunction "OSC2_2") (pintype "unspecified"))
    )
    (net (code "102") (name "Net-(U15-XO)") (class "Default")
      (node (ref "C38") (pin "1") (pinfunction "1_1") (pintype "unspecified"))
      (node (ref "U15") (pin "8") (pinfunction "XO_8") (pintype "unspecified"))
      (node (ref "Y1") (pin "1") (pinfunction "OSC1_1") (pintype "unspecified"))
    )
    (net (code "103") (name "VIN_24V") (class "Default")
      (node (ref "C6") (pin "1") (pintype "unspecified"))
      (node (ref "C7") (pin "2") (pinfunction "2_2") (pintype "unspecified"))
      (node (ref "D3") (pin "2") (pinfunction "2_2") (pintype "unspecified"))
      (node (ref "U2") (pin "1") (pinfunction "VIN_1") (pintype "input"))
    )
    (net (code "104") (name "VUSB") (class "Default")
      (node (ref "D11") (pin "2") (pinfunction "A_2") (pintype "input"))
      (node (ref "P18") (pin "1") (pinfunction "VBUS_1") (pintype "unspecified"))
      (node (ref "U17") (pin "5") (pinfunction "5_5") (pintype "unspecified"))
    )
    (net (code "105") (name "unconnected-(DB1-MH1-Pad10)") (class "Default")
      (node (ref "DB1") (pin "10") (pinfunction "MH1_10") (pintype "input"))
    )
    (net (code "106") (name "unconnected-(DB1-MH2-Pad11)") (class "Default")
      (node (ref "DB1") (pin "11") (pinfunction "MH2_11") (pintype "input"))
    )
    (net (code "107") (name "unconnected-(DB1-Pad1)") (class "Default")
      (node (ref "DB1") (pin "1") (pinfunction "1_1") (pintype "input"))
    )
    (net (code "108") (name "unconnected-(DB1-Pad6)") (class "Default")
      (node (ref "DB1") (pin "6") (pinfunction "6_6") (pintype "input"))
    )
    (net (code "109") (name "unconnected-(DB1-Pad7)") (class "Default")
      (node (ref "DB1") (pin "7") (pinfunction "7_7") (pintype "input"))
    )
    (net (code "110") (name "unconnected-(H8-Pad2)") (class "Default")
      (node (ref "H8") (pin "2") (pinfunction "2_2") (pintype "unspecified"))
    )
    (net (code "111") (name "unconnected-(U4-NC-Pad1)") (class "Default")
      (node (ref "U4") (pin "1") (pinfunction "NC_1") (pintype "unspecified"))
    )
    (net (code "112") (name "unconnected-(U5-NC-Pad1)") (class "Default")
      (node (ref "U5") (pin "1") (pinfunction "NC_1") (pintype "unspecified"))
    )
    (net (code "113") (name "unconnected-(U7-NC-Pad1)") (class "Default")
      (node (ref "U7") (pin "1") (pinfunction "NC_1") (pintype "unspecified"))
    )
    (net (code "114") (name "unconnected-(U8-Q0-Pad15)") (class "Default")
      (node (ref "U8") (pin "15") (pinfunction "Q0_15") (pintype "unspecified"))
    )
    (net (code "115") (name "unconnected-(U8-Q7S-Pad9)") (class "Default")
      (node (ref "U8") (pin "9") (pinfunction "Q7S_9") (pintype "unspecified"))
    )
    (net (code "116") (name "unconnected-(U9-CLK-Pad20)") (class "Default")
      (node (ref "U9") (pin "20") (pinfunction "CLK_20") (pintype "unspecified"))
    )
    (net (code "117") (name "unconnected-(U9-CMD-Pad19)") (class "Default")
      (node (ref "U9") (pin "19") (pinfunction "CMD_19") (pintype "unspecified"))
    )
    (net (code "118") (name "unconnected-(U9-NC-Pad32)") (class "Default")
      (node (ref "U9") (pin "32") (pinfunction "NC_32") (pintype "unspecified"))
    )
    (net (code "119") (name "unconnected-(U9-SD0-Pad21)") (class "Default")
      (node (ref "U9") (pin "21") (pinfunction "SD0_21") (pintype "unspecified"))
    )
    (net (code "120") (name "unconnected-(U9-SD1-Pad22)") (class "Default")
      (node (ref "U9") (pin "22") (pinfunction "SD1_22") (pintype "unspecified"))
    )
    (net (code "121") (name "unconnected-(U9-SD2-Pad17)") (class "Default")
      (node (ref "U9") (pin "17") (pinfunction "SD2_17") (pintype "unspecified"))
    )
    (net (code "122") (name "unconnected-(U9-SD3-Pad18)") (class "Default")
      (node (ref "U9") (pin "18") (pinfunction "SD3_18") (pintype "unspecified"))
    )
    (net (code "123") (name "unconnected-(U11-NC-Pad1)") (class "Default")
      (node (ref "U11") (pin "1") (pinfunction "NC_1") (pintype "unspecified"))
    )
    (net (code "124") (name "unconnected-(U12-R2OUT-Pad9)") (class "Default")
      (node (ref "U12") (pin "9") (pinfunction "R2OUT_9") (pintype "unspecified"))
    )
    (net (code "125") (name "unconnected-(U12-T2IN-Pad10)") (class "Default")
      (node (ref "U12") (pin "10") (pinfunction "T2IN_10") (pintype "unspecified"))
    )
    (net (code "126") (name "unconnected-(U13-NC-Pad1)") (class "Default")
      (node (ref "U13") (pin "1") (pinfunction "NC_1") (pintype "unspecified"))
    )
    (net (code "127") (name "unconnected-(U14-NC-Pad1)") (class "Default")
      (node (ref "U14") (pin "1") (pinfunction "NC_1") (pintype "unspecified"))
    )
    (net (code "128") (name "unconnected-(U15-CTS#-Pad9)") (class "Default")
      (node (ref "U15") (pin "9") (pinfunction "CTS#_9") (pintype "unspecified"))
    )
    (net (code "129") (name "unconnected-(U15-DCD#-Pad12)") (class "Default")
      (node (ref "U15") (pin "12") (pinfunction "DCD#_12") (pintype "unspecified"))
    )
    (net (code "130") (name "unconnected-(U15-DSR#-Pad10)") (class "Default")
      (node (ref "U15") (pin "10") (pinfunction "DSR#_10") (pintype "unspecified"))
    )
    (net (code "131") (name "unconnected-(U15-R232-Pad15)") (class "Default")
      (node (ref "U15") (pin "15") (pinfunction "R232_15") (pintype "unspecified"))
    )
    (net (code "132") (name "unconnected-(U15-RI#-Pad11)") (class "Default")
      (node (ref "U15") (pin "11") (pinfunction "RI#_11") (pintype "unspecified"))
    )
    (net (code "133") (name "unconnected-(U16-DAT1-Pad8)") (class "Default")
      (node (ref "U16") (pin "8") (pinfunction "DAT1_8") (pintype "unspecified"))
    )
    (net (code "134") (name "unconnected-(U16-DAT2-Pad1)") (class "Default")
      (node (ref "U16") (pin "1") (pinfunction "DAT2_1") (pintype "unspecified"))
    )
  )
)
